# Sheet1.net
KiCad netlist of a schematic drawn in Altium Designer
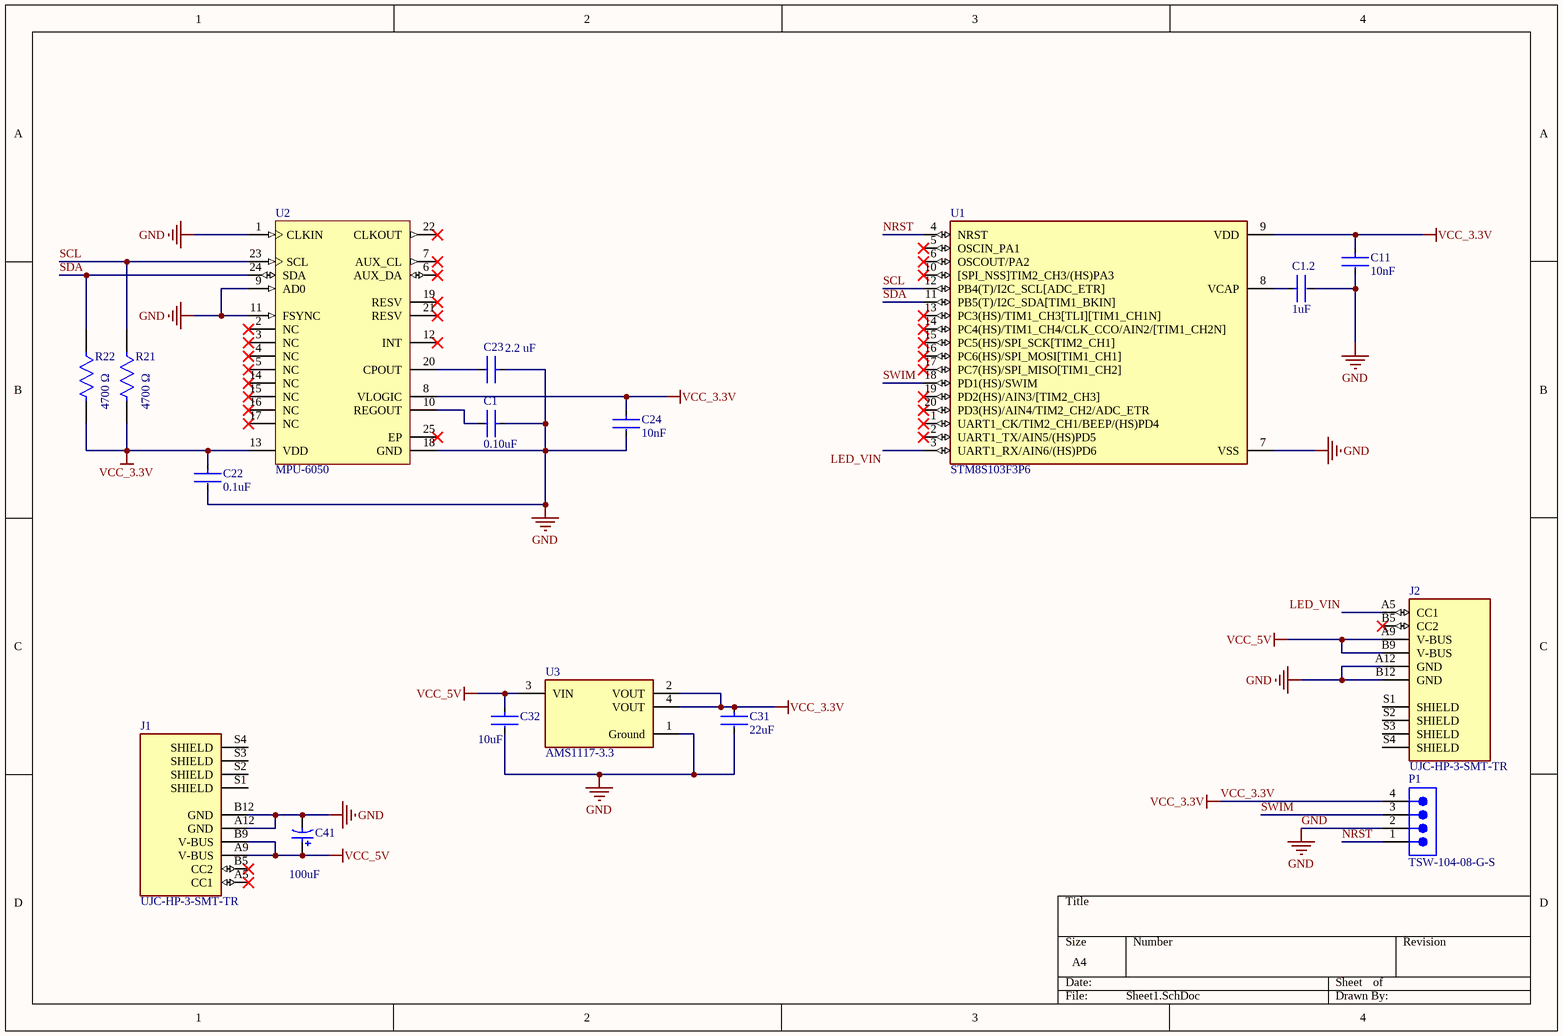
[diagram p0: Sheet1.SchDoc]

(export (version "E")
  (design (tool "Eeschema 10.0.6"))
  (components
    (comp (ref "C1")
      (value "0.10uF")
      (footprint "FP-GRM033-0_03-IPC_A")
      (description "Chip Multilayer Ceramic Capacitors for General Purpose, 0201, 0.10uF, X6S, 22%, 10%, 4V")
      (fields (field (name "TOLERANCE") "10%"))
      (libsource (lib "Altium Content Vault") (part "b4654b650e69147ec39a6b967a45e02"))
    )
    (comp (ref "C1.2")
      (value "1uF")
      (footprint "FP-GCG31C-0_3-IPC_A")
      (libsource (lib "Altium Content Vault") (part "02cd4be3c70576c341d710602a673aa"))
    )
    (comp (ref "C11")
      (value "10nF")
      (footprint "FP-GRM155-0_05-IPC_C")
      (description "Chip Multilayer Ceramic Capacitors for General Purpose, 0402, 10000pF, X7R, 15%, 10%, 50V")
      (fields (field (name "TOLERANCE") "10%") (field (name "VOLTAGE") "25V"))
      (libsource (lib "Altium Content Vault") (part "02cd4be3c70576c341d710602a673aa"))
    )
    (comp (ref "C22")
      (value "0.1uF")
      (footprint "FP-GRM033-0_03-IPC_A")
      (description "Chip Multilayer Ceramic Capacitors for General Purpose, 0201, 0.10uF, X6S, 22%, 10%, 4V")
      (fields (field (name "TOLERANCE") "10%"))
      (libsource (lib "Altium Content Vault") (part "b4654b650e69147ec39a6b967a45e02"))
    )
    (comp (ref "C23")
      (value "2.2 uF")
      (footprint "FP-CGA6P-IPC_C")
      (description "Cap Ceramic 2.2uF 50V X7R 10% Pad SMD 1210 +125°C Automotive T/R")
      (fields (field (name "TOLERANCE") "10%"))
      (libsource (lib "Altium Content Vault") (part "b4654b650e69147ec39a6b967a45e02"))
    )
    (comp (ref "C24")
      (value "10nF")
      (footprint "FP-GRM155-0_05-IPC_C")
      (description "Chip Multilayer Ceramic Capacitors for General Purpose, 0402, 10000pF, X7R, 15%, 10%, 50V")
      (fields (field (name "TOLERANCE") "10%") (field (name "VOLTAGE") "25V"))
      (libsource (lib "Altium Content Vault") (part "02cd4be3c70576c341d710602a673aa"))
    )
    (comp (ref "C31")
      (value "22uF")
      (footprint "FP-GRM188-0_2-IPC_C")
      (description "Chip Multilayer Ceramic Capacitors for General Purpose, 0603, 22uF, X5R, 15%, 20%, 10V")
      (fields (field (name "TOLERANCE") "20%"))
      (libsource (lib "Altium Content Vault") (part "11868f565c42a9108669ba33697ecf6"))
    )
    (comp (ref "C32")
      (value "10uF")
      (footprint "FP-GRM188-0_1-e0_2_0_55-IPC_A")
      (description "Chip Multilayer Ceramic Capacitors for General Purpose, 0603, 10uF, X5R, 15%, 20%, 6.3V")
      (fields (field (name "VOLTAGE") "6.3V") (field (name "TOLERANCE") "20%"))
      (libsource (lib "Altium Content Vault") (part "02cd4be3c70576c341d710602a673aa"))
    )
    (comp (ref "C41")
      (value "100uF")
      (footprint "PNSC-FK-V-D8_V")
      (fields (field (name "MANUFACTURER") "Panasonic"))
      (libsource (lib "Altium Content Vault") (part "CAP-P-2"))
    )
    (comp (ref "J1")
      (value "UJC-HP-3-SMT-TR")
      (footprint "CUI_UJC-HP-3-SMT-TR")
      (libsource (lib "") (part "UJC-HP-3-SMT-TR_1"))
    )
    (comp (ref "J2")
      (value "UJC-HP-3-SMT-TR")
      (footprint "CUI_UJC-HP-3-SMT-TR")
      (libsource (lib "UJC-HP-3-SMT-TR") (part "UJC-HP-3-SMT-TR"))
    )
    (comp (ref "P1")
      (value "TSW-104-08-G-S")
      (footprint "SMTC-TSW-104-08-X-S")
      (description "0.025\" SQ Post Header, Through-hole, Vertical, -55 to 125 degC, 2.54 mm Pitch, 4-Pin, Male, RoHS")
      (fields (field (name "MANUFACTURER") "Samtec"))
      (libsource (lib "Altium Content Vault") (part "SMTC-TSW-104-08-X-S"))
    )
    (comp (ref "R21")
      (value "4700 Ω")
      (footprint "FP-RC1206-0_65-IPC_B")
      (description "RES SMD 4.7K OHM 1% 1/4W 1206")
      (fields (field (name "TOLERANCE") "1%"))
      (libsource (lib "Altium Content Vault") (part "1029c3af85768c4190bb7ad29bc67b5"))
    )
    (comp (ref "R22")
      (value "4700 Ω")
      (footprint "FP-RC1206-0_65-IPC_B")
      (description "RES SMD 4.7K OHM 1% 1/4W 1206")
      (fields (field (name "TOLERANCE") "1%"))
      (libsource (lib "Altium Content Vault") (part "1029c3af85768c4190bb7ad29bc67b5"))
    )
    (comp (ref "U1")
      (value "STM8S103F3P6")
      (footprint "SOP65P640X120-20N")
      (description "STM8 series Microcontroller IC 8-Bit 16MHz 8KB (8K x 8) FLASH 20-TSSOP")
      (fields (field (name "MF") "STMicroelectronics"))
      (libsource (lib "STM8S103F3P6") (part "STM8S103F3P6"))
    )
    (comp (ref "U2")
      (value "MPU-6050")
      (footprint "IS-QFN-24_V")
      (fields (field (name "MANUFACTURER") "InvenSense"))
      (libsource (lib "Altium Content Vault") (part "IS-MPU-6050-QFN-24"))
    )
    (comp (ref "U3")
      (value "AMS1117-3.3")
      (footprint "FP-AMS1117-IPC_C")
      (description "LDO Voltage Regulators 1A, 3.3V")
      (fields
        (field (name "OCTOPART") "https://octopart.com/ams1117-3.3-advanced+monolithic+systems-25899300")
        (field (name "MANUFACTURER") "Advanced Monolithic Systems")
      )
      (libsource (lib "Altium Content Vault") (part "8bdbb5f8e77002000e30dd2845d0354"))
    )
  )
  (nets
    (net (code "1") (name "/LED_VIN") (class "Default")
      (node (ref "J2") (pin "A5") (pinfunction "CC1_A5") (pintype "bidirectional"))
      (node (ref "U1") (pin "3") (pinfunction "UART1_RX/AIN6/(HS)PD6_3") (pintype "bidirectional"))
    )
    (net (code "2") (name "/NRST") (class "Default")
      (node (ref "P1") (pin "1") (pinfunction "1_1") (pintype "passive"))
      (node (ref "U1") (pin "4") (pinfunction "NRST_4") (pintype "bidirectional"))
    )
    (net (code "3") (name "/SCL") (class "Default")
      (node (ref "R21") (pin "1") (pinfunction "1_1") (pintype "passive"))
      (node (ref "U1") (pin "12") (pinfunction "PB4(T)/I2C_SCL[ADC_ETR]_12") (pintype "bidirectional"))
      (node (ref "U2") (pin "23") (pinfunction "SCL_23") (pintype "input"))
    )
    (net (code "4") (name "/SDA") (class "Default")
      (node (ref "R22") (pin "1") (pinfunction "1_1") (pintype "passive"))
      (node (ref "U1") (pin "11") (pinfunction "PB5(T)/I2C_SDA[TIM1_BKIN]_11") (pintype "bidirectional"))
      (node (ref "U2") (pin "24") (pinfunction "SDA_24") (pintype "bidirectional"))
    )
    (net (code "5") (name "/SWIM") (class "Default")
      (node (ref "P1") (pin "3") (pinfunction "3_3") (pintype "passive"))
      (node (ref "U1") (pin "18") (pinfunction "PD1(HS)/SWIM_18") (pintype "bidirectional"))
    )
    (net (code "6") (name "GND") (class "Default")
      (node (ref "C1") (pin "1") (pinfunction "1_1") (pintype "passive"))
      (node (ref "C1.2") (pin "2") (pinfunction "2_2") (pintype "passive"))
      (node (ref "C11") (pin "2") (pinfunction "2_2") (pintype "passive"))
      (node (ref "C22") (pin "2") (pinfunction "2_2") (pintype "passive"))
      (node (ref "C23") (pin "1") (pinfunction "1_1") (pintype "passive"))
      (node (ref "C24") (pin "2") (pinfunction "2_2") (pintype "passive"))
      (node (ref "C31") (pin "2") (pinfunction "2_2") (pintype "passive"))
      (node (ref "C32") (pin "2") (pinfunction "2_2") (pintype "passive"))
      (node (ref "C41") (pin "2") (pinfunction "2_2") (pintype "passive"))
      (node (ref "J1") (pin "A12") (pinfunction "GND_A12") (pintype "power_in"))
      (node (ref "J1") (pin "B12") (pinfunction "GND_B12") (pintype "power_in"))
      (node (ref "J2") (pin "A12") (pinfunction "GND_A12") (pintype "power_in"))
      (node (ref "J2") (pin "B12") (pinfunction "GND_B12") (pintype "power_in"))
      (node (ref "P1") (pin "2") (pinfunction "2_2") (pintype "passive"))
      (node (ref "U1") (pin "7") (pinfunction "VSS_7") (pintype "power_in"))
      (node (ref "U2") (pin "1") (pinfunction "CLKIN_1") (pintype "input"))
      (node (ref "U2") (pin "11") (pinfunction "FSYNC_11") (pintype "input"))
      (node (ref "U2") (pin "18") (pinfunction "GND_18") (pintype "power_in"))
      (node (ref "U2") (pin "9") (pinfunction "AD0_9") (pintype "input"))
      (node (ref "U3") (pin "1") (pinfunction "Ground_1") (pintype "power_in"))
    )
    (net (code "7") (name "Net-(U1-VCAP)") (class "Default")
      (node (ref "C1.2") (pin "1") (pinfunction "1_1") (pintype "passive"))
      (node (ref "U1") (pin "8") (pinfunction "VCAP_8") (pintype "passive"))
    )
    (net (code "8") (name "Net-(U2-CPOUT)") (class "Default")
      (node (ref "C23") (pin "2") (pinfunction "2_2") (pintype "passive"))
      (node (ref "U2") (pin "20") (pinfunction "CPOUT_20") (pintype "passive"))
    )
    (net (code "9") (name "Net-(U2-REGOUT)") (class "Default")
      (node (ref "C1") (pin "2") (pinfunction "2_2") (pintype "passive"))
      (node (ref "U2") (pin "10") (pinfunction "REGOUT_10") (pintype "passive"))
    )
    (net (code "10") (name "VCC_3.3V") (class "Default")
      (node (ref "C11") (pin "1") (pinfunction "1_1") (pintype "passive"))
      (node (ref "C22") (pin "1") (pinfunction "1_1") (pintype "passive"))
      (node (ref "C24") (pin "1") (pinfunction "1_1") (pintype "passive"))
      (node (ref "C31") (pin "1") (pinfunction "1_1") (pintype "passive"))
      (node (ref "P1") (pin "4") (pinfunction "4_4") (pintype "passive"))
      (node (ref "R21") (pin "2") (pinfunction "2_2") (pintype "passive"))
      (node (ref "R22") (pin "2") (pinfunction "2_2") (pintype "passive"))
      (node (ref "U1") (pin "9") (pinfunction "VDD_9") (pintype "power_in"))
      (node (ref "U2") (pin "13") (pinfunction "VDD_13") (pintype "power_in"))
      (node (ref "U2") (pin "8") (pinfunction "VLOGIC_8") (pintype "power_in"))
      (node (ref "U3") (pin "2") (pinfunction "VOUT_2") (pintype "passive"))
      (node (ref "U3") (pin "4") (pinfunction "VOUT_4") (pintype "passive"))
    )
    (net (code "11") (name "VCC_5V") (class "Default")
      (node (ref "C32") (pin "1") (pinfunction "1_1") (pintype "passive"))
      (node (ref "C41") (pin "1") (pinfunction "1_1") (pintype "passive"))
      (node (ref "J1") (pin "A9") (pinfunction "V-BUS_A9") (pintype "power_in"))
      (node (ref "J1") (pin "B9") (pinfunction "V-BUS_B9") (pintype "power_in"))
      (node (ref "J2") (pin "A9") (pinfunction "V-BUS_A9") (pintype "power_in"))
      (node (ref "J2") (pin "B9") (pinfunction "V-BUS_B9") (pintype "power_in"))
      (node (ref "U3") (pin "3") (pinfunction "VIN_3") (pintype "power_in"))
    )
    (net (code "12") (name "unconnected-(J1-CC1-PadA5)") (class "Default")
      (node (ref "J1") (pin "A5") (pinfunction "CC1_A5") (pintype "bidirectional+no_connect"))
    )
    (net (code "13") (name "unconnected-(J1-CC2-PadB5)") (class "Default")
      (node (ref "J1") (pin "B5") (pinfunction "CC2_B5") (pintype "bidirectional+no_connect"))
    )
    (net (code "14") (name "unconnected-(J1-SHIELD-PadS1)") (class "Default")
      (node (ref "J1") (pin "S1") (pinfunction "SHIELD_S1") (pintype "passive"))
    )
    (net (code "15") (name "unconnected-(J1-SHIELD-PadS2)") (class "Default")
      (node (ref "J1") (pin "S2") (pinfunction "SHIELD_S2") (pintype "passive"))
    )
    (net (code "16") (name "unconnected-(J1-SHIELD-PadS3)") (class "Default")
      (node (ref "J1") (pin "S3") (pinfunction "SHIELD_S3") (pintype "passive"))
    )
    (net (code "17") (name "unconnected-(J1-SHIELD-PadS4)") (class "Default")
      (node (ref "J1") (pin "S4") (pinfunction "SHIELD_S4") (pintype "passive"))
    )
    (net (code "18") (name "unconnected-(J2-CC2-PadB5)") (class "Default")
      (node (ref "J2") (pin "B5") (pinfunction "CC2_B5") (pintype "bidirectional+no_connect"))
    )
    (net (code "19") (name "unconnected-(J2-SHIELD-PadS1)") (class "Default")
      (node (ref "J2") (pin "S1") (pinfunction "SHIELD_S1") (pintype "passive"))
    )
    (net (code "20") (name "unconnected-(J2-SHIELD-PadS2)") (class "Default")
      (node (ref "J2") (pin "S2") (pinfunction "SHIELD_S2") (pintype "passive"))
    )
    (net (code "21") (name "unconnected-(J2-SHIELD-PadS3)") (class "Default")
      (node (ref "J2") (pin "S3") (pinfunction "SHIELD_S3") (pintype "passive"))
    )
    (net (code "22") (name "unconnected-(J2-SHIELD-PadS4)") (class "Default")
      (node (ref "J2") (pin "S4") (pinfunction "SHIELD_S4") (pintype "passive"))
    )
    (net (code "23") (name "unconnected-(U1-OSCIN_PA1-Pad5)") (class "Default")
      (node (ref "U1") (pin "5") (pinfunction "OSCIN_PA1_5") (pintype "bidirectional+no_connect"))
    )
    (net (code "24") (name "unconnected-(U1-OSCOUT{slash}PA2-Pad6)") (class "Default")
      (node (ref "U1") (pin "6") (pinfunction "OSCOUT/PA2_6") (pintype "bidirectional+no_connect"))
    )
    (net (code "25") (name "unconnected-(U1-PC3(HS){slash}TIM1_CH3[TLI][TIM1_CH1N]-Pad13)") (class "Default")
      (node (ref "U1") (pin "13") (pinfunction "PC3(HS)/TIM1_CH3[TLI][TIM1_CH1N]_13") (pintype "bidirectional+no_connect"))
    )
    (net (code "26") (name "unconnected-(U1-PC4(HS){slash}TIM1_CH4{slash}CLK_CCO{slash}AIN2{slash}[TIM1_CH2N]-Pad14)") (class "Default")
      (node (ref "U1") (pin "14") (pinfunction "PC4(HS)/TIM1_CH4/CLK_CCO/AIN2/[TIM1_CH2N]_14") (pintype "bidirectional+no_connect"))
    )
    (net (code "27") (name "unconnected-(U1-PC5(HS){slash}SPI_SCK[TIM2_CH1]-Pad15)") (class "Default")
      (node (ref "U1") (pin "15") (pinfunction "PC5(HS)/SPI_SCK[TIM2_CH1]_15") (pintype "bidirectional+no_connect"))
    )
    (net (code "28") (name "unconnected-(U1-PC6(HS){slash}SPI_MOSI[TIM1_CH1]-Pad16)") (class "Default")
      (node (ref "U1") (pin "16") (pinfunction "PC6(HS)/SPI_MOSI[TIM1_CH1]_16") (pintype "bidirectional+no_connect"))
    )
    (net (code "29") (name "unconnected-(U1-PC7(HS){slash}SPI_MISO[TIM1_CH2]-Pad17)") (class "Default")
      (node (ref "U1") (pin "17") (pinfunction "PC7(HS)/SPI_MISO[TIM1_CH2]_17") (pintype "bidirectional+no_connect"))
    )
    (net (code "30") (name "unconnected-(U1-PD2(HS){slash}AIN3{slash}[TIM2_CH3]-Pad19)") (class "Default")
      (node (ref "U1") (pin "19") (pinfunction "PD2(HS)/AIN3/[TIM2_CH3]_19") (pintype "bidirectional+no_connect"))
    )
    (net (code "31") (name "unconnected-(U1-PD3(HS){slash}AIN4{slash}TIM2_CH2{slash}ADC_ETR-Pad20)") (class "Default")
      (node (ref "U1") (pin "20") (pinfunction "PD3(HS)/AIN4/TIM2_CH2/ADC_ETR_20") (pintype "bidirectional+no_connect"))
    )
    (net (code "32") (name "unconnected-(U1-UART1_CK{slash}TIM2_CH1{slash}BEEP{slash}(HS)PD4-Pad1)") (class "Default")
      (node (ref "U1") (pin "1") (pinfunction "UART1_CK/TIM2_CH1/BEEP/(HS)PD4_1") (pintype "bidirectional+no_connect"))
    )
    (net (code "33") (name "unconnected-(U1-UART1_TX{slash}AIN5{slash}(HS)PD5-Pad2)") (class "Default")
      (node (ref "U1") (pin "2") (pinfunction "UART1_TX/AIN5/(HS)PD5_2") (pintype "bidirectional+no_connect"))
    )
    (net (code "34") (name "unconnected-(U1-[SPI_NSS]TIM2_CH3{slash}(HS)PA3-Pad10)") (class "Default")
      (node (ref "U1") (pin "10") (pinfunction "[SPI_NSS]TIM2_CH3/(HS)PA3_10") (pintype "bidirectional+no_connect"))
    )
    (net (code "35") (name "unconnected-(U2-AUX_CL-Pad7)") (class "Default")
      (node (ref "U2") (pin "7") (pinfunction "AUX_CL_7") (pintype "output+no_connect"))
    )
    (net (code "36") (name "unconnected-(U2-AUX_DA-Pad6)") (class "Default")
      (node (ref "U2") (pin "6") (pinfunction "AUX_DA_6") (pintype "bidirectional+no_connect"))
    )
    (net (code "37") (name "unconnected-(U2-CLKOUT-Pad22)") (class "Default")
      (node (ref "U2") (pin "22") (pinfunction "CLKOUT_22") (pintype "output+no_connect"))
    )
    (net (code "38") (name "unconnected-(U2-EP-Pad25)") (class "Default")
      (node (ref "U2") (pin "25") (pinfunction "EP_25") (pintype "power_in+no_connect"))
    )
    (net (code "39") (name "unconnected-(U2-INT-Pad12)") (class "Default")
      (node (ref "U2") (pin "12") (pinfunction "INT_12") (pintype "open_collector+no_connect"))
    )
    (net (code "40") (name "unconnected-(U2-NC-Pad2)") (class "Default")
      (node (ref "U2") (pin "2") (pinfunction "NC_2") (pintype "passive+no_connect"))
    )
    (net (code "41") (name "unconnected-(U2-NC-Pad3)") (class "Default")
      (node (ref "U2") (pin "3") (pinfunction "NC_3") (pintype "passive+no_connect"))
    )
    (net (code "42") (name "unconnected-(U2-NC-Pad4)") (class "Default")
      (node (ref "U2") (pin "4") (pinfunction "NC_4") (pintype "passive+no_connect"))
    )
    (net (code "43") (name "unconnected-(U2-NC-Pad5)") (class "Default")
      (node (ref "U2") (pin "5") (pinfunction "NC_5") (pintype "passive+no_connect"))
    )
    (net (code "44") (name "unconnected-(U2-NC-Pad14)") (class "Default")
      (node (ref "U2") (pin "14") (pinfunction "NC_14") (pintype "passive+no_connect"))
    )
    (net (code "45") (name "unconnected-(U2-NC-Pad15)") (class "Default")
      (node (ref "U2") (pin "15") (pinfunction "NC_15") (pintype "passive+no_connect"))
    )
    (net (code "46") (name "unconnected-(U2-NC-Pad16)") (class "Default")
      (node (ref "U2") (pin "16") (pinfunction "NC_16") (pintype "passive+no_connect"))
    )
    (net (code "47") (name "unconnected-(U2-NC-Pad17)") (class "Default")
      (node (ref "U2") (pin "17") (pinfunction "NC_17") (pintype "passive+no_connect"))
    )
    (net (code "48") (name "unconnected-(U2-RESV-Pad19)") (class "Default")
      (node (ref "U2") (pin "19") (pinfunction "RESV_19") (pintype "passive+no_connect"))
    )
    (net (code "49") (name "unconnected-(U2-RESV-Pad21)") (class "Default")
      (node (ref "U2") (pin "21") (pinfunction "RESV_21") (pintype "passive+no_connect"))
    )
  )
)
